# ventmon_t0_5b.net
KiCad netlist of a schematic drawn in EAGLE
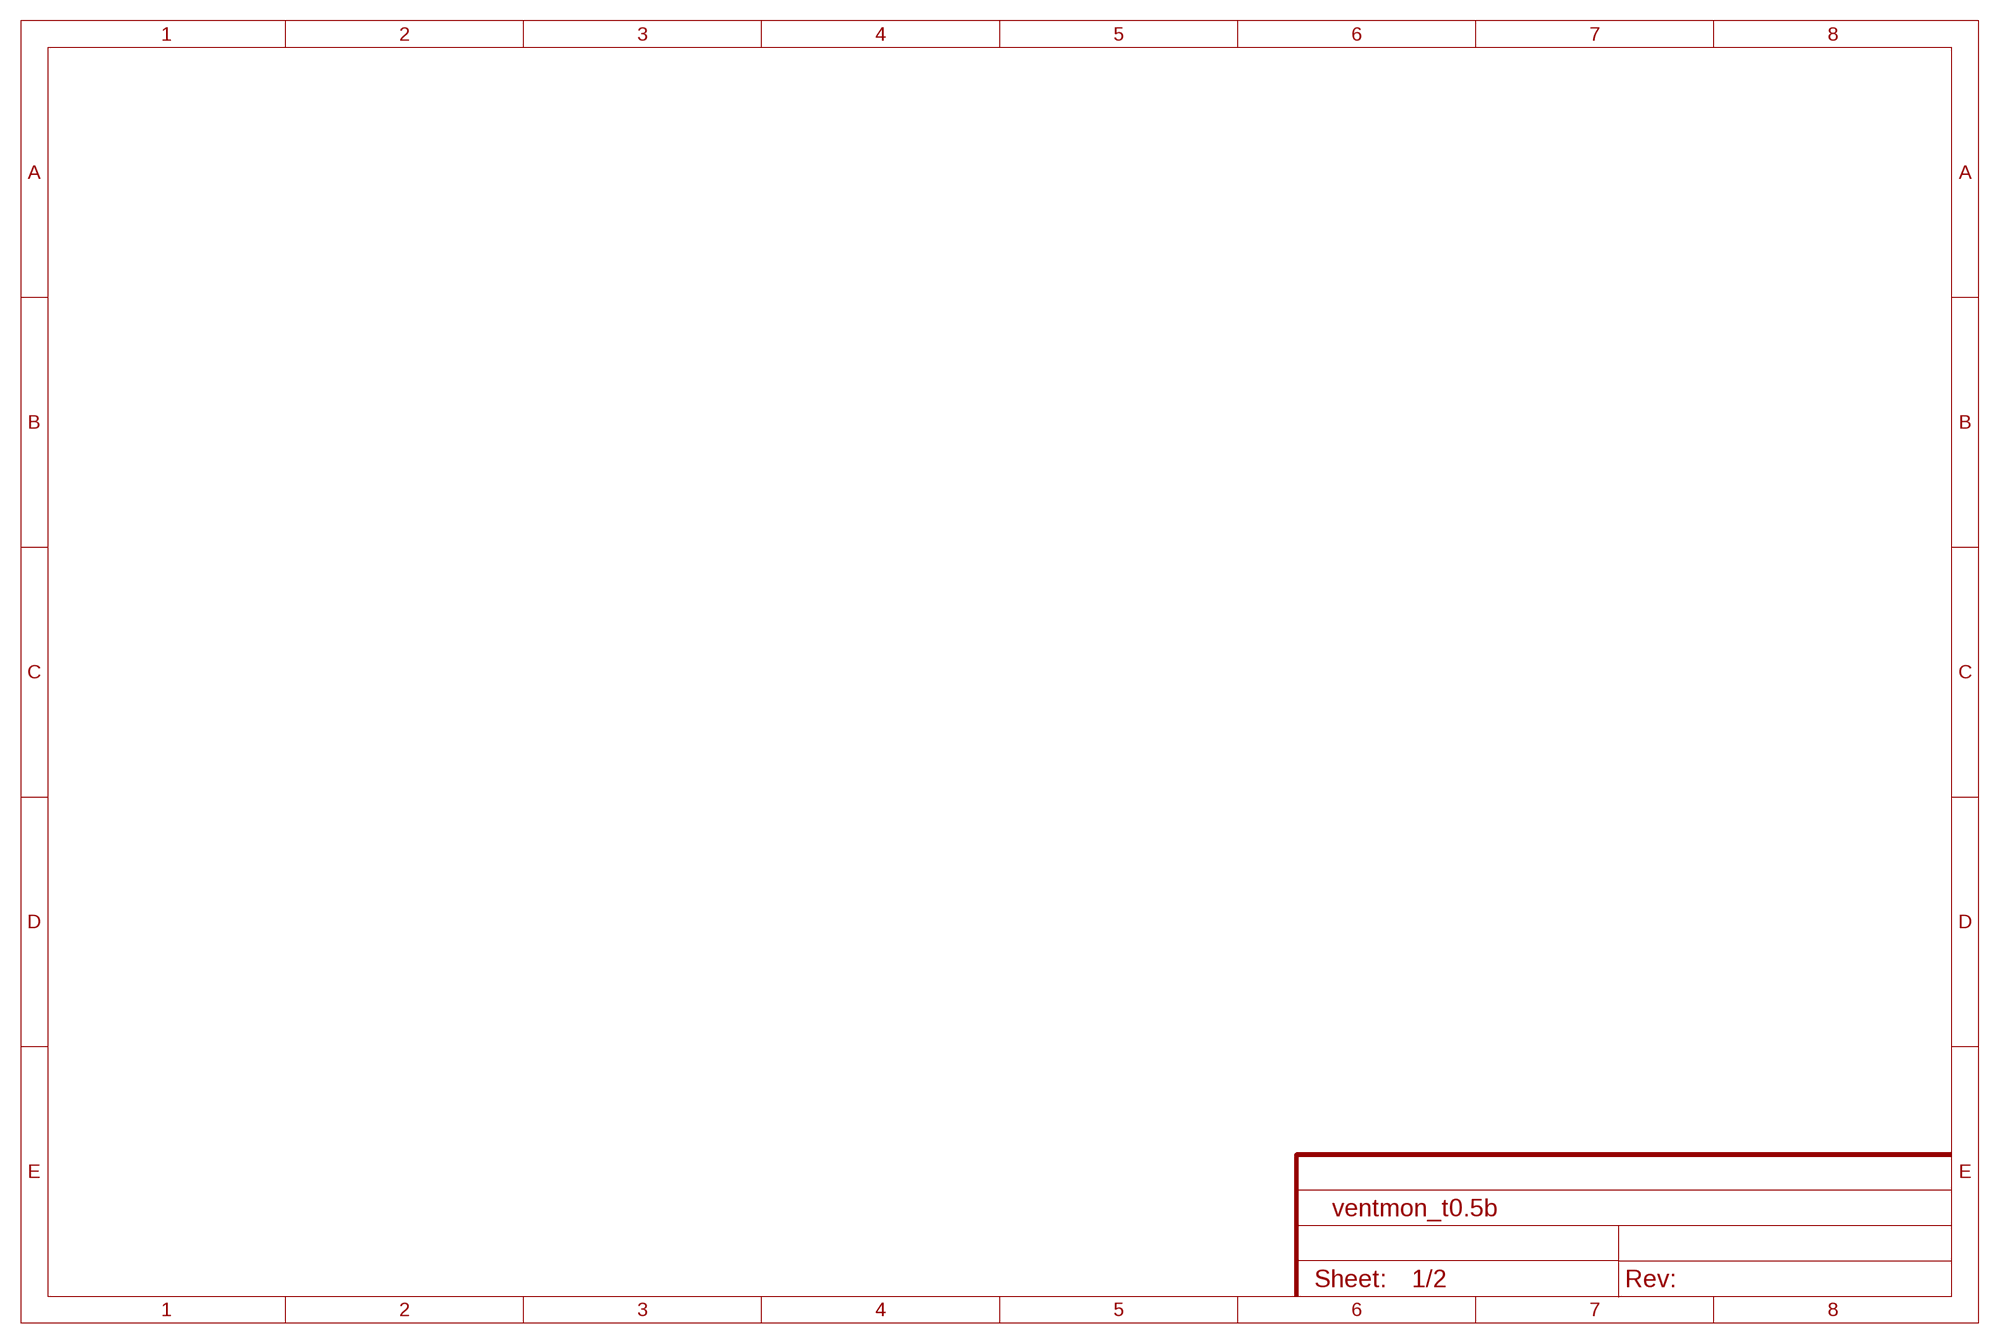
[diagram p0: schematic, sheet 1]
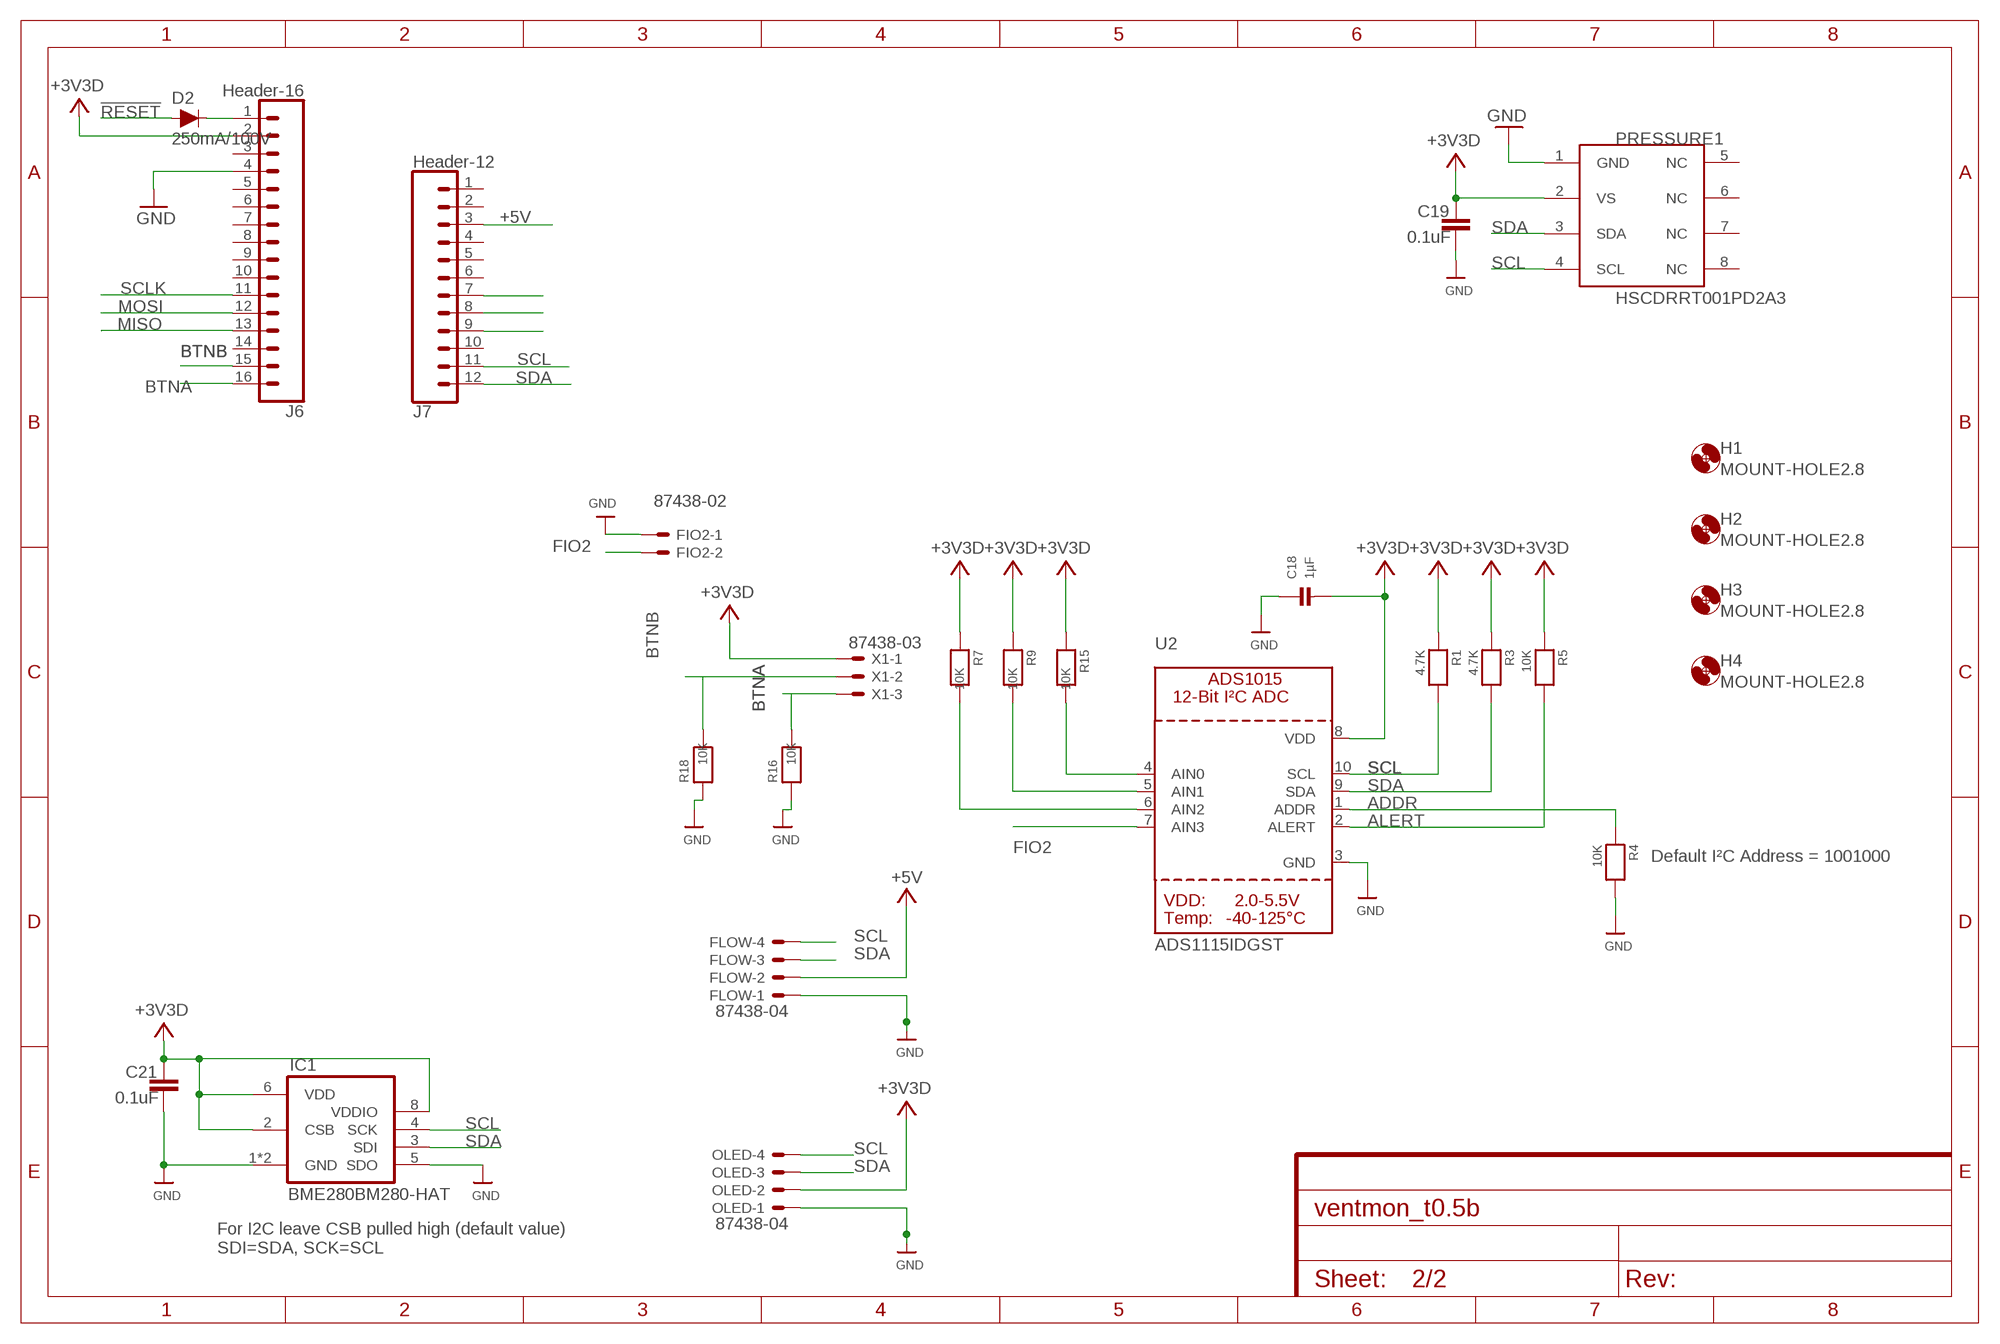
[diagram p1: schematic, sheet 2]

(export (version "E")
  (design (tool "Eeschema 10.0.6"))
  (components
    (comp (ref "C18")
      (value "1µF")
      (footprint "eagle-import:0603")
      (libsource (lib "eagle-import") (part "CAP_CERAMIC0603"))
    )
    (comp (ref "C19")
      (value "0.1uF")
      (footprint "eagle-import:C0402_B")
      (libsource (lib "eagle-import") (part "CAP_1"))
    )
    (comp (ref "C21")
      (value "0.1uF")
      (footprint "eagle-import:C0402_B")
      (libsource (lib "eagle-import") (part "CAP_1"))
    )
    (comp (ref "D2")
      (value "250mA/100V")
      (footprint "eagle-import:SOD-323")
      (libsource (lib "eagle-import") (part "DIODE-BAS16J"))
    )
    (comp (ref "FIO2")
      (value "87438-02")
      (footprint "eagle-import:87438-02")
      (fields (field (name "MF") "MOLEX"))
      (libsource (lib "eagle-import") (part "87438-02"))
    )
    (comp (ref "FLOW")
      (value "87438-04")
      (footprint "eagle-import:87438-04")
      (fields (field (name "MF") "MOLEX"))
      (libsource (lib "eagle-import") (part "87438-04"))
    )
    (comp (ref "H1")
      (value "MOUNT-HOLE2.8")
      (footprint "eagle-import:2,8")
      (fields (field (name "SPICEPREFIX") "X"))
      (libsource (lib "eagle-import") (part "MOUNT-HOLE2.8"))
    )
    (comp (ref "H2")
      (value "MOUNT-HOLE2.8")
      (footprint "eagle-import:2,8")
      (libsource (lib "eagle-import") (part "MOUNT-HOLE2.8"))
    )
    (comp (ref "H3")
      (value "MOUNT-HOLE2.8")
      (footprint "eagle-import:2,8")
      (libsource (lib "eagle-import") (part "MOUNT-HOLE2.8"))
    )
    (comp (ref "H4")
      (value "MOUNT-HOLE2.8")
      (footprint "eagle-import:2,8")
      (libsource (lib "eagle-import") (part "MOUNT-HOLE2.8"))
    )
    (comp (ref "IC1")
      (value "BME280BM280-HAT")
      (footprint "eagle-import:BME280-HAT")
      (libsource (lib "eagle-import") (part "BME280BM280-HAT"))
    )
    (comp (ref "J6")
      (value "Header-16")
      (footprint "eagle-import:1X16")
      (libsource (lib "eagle-import") (part "CONN_16"))
    )
    (comp (ref "J7")
      (value "Header-12")
      (footprint "eagle-import:1X12")
      (libsource (lib "eagle-import") (part "CONN_12"))
    )
    (comp (ref "OLED")
      (value "87438-04")
      (footprint "eagle-import:87438-04")
      (fields (field (name "MF") "MOLEX"))
      (libsource (lib "eagle-import") (part "87438-04"))
    )
    (comp (ref "PRESSURE1")
      (value "HSCDRRT001PD2A3")
      (footprint "eagle-import:DIP1330W46P254L1000H616Q8B")
      (libsource (lib "eagle-import") (part "HSCDRRT001PD2A3"))
    )
    (comp (ref "R1")
      (value "4.7K")
      (footprint "eagle-import:0603")
      (libsource (lib "eagle-import") (part "RESISTOR0603"))
    )
    (comp (ref "R3")
      (value "4.7K")
      (footprint "eagle-import:0603")
      (libsource (lib "eagle-import") (part "RESISTOR0603"))
    )
    (comp (ref "R4")
      (value "10K")
      (footprint "eagle-import:0603")
      (libsource (lib "eagle-import") (part "RESISTOR0603"))
    )
    (comp (ref "R5")
      (value "10K")
      (footprint "eagle-import:0603")
      (libsource (lib "eagle-import") (part "RESISTOR0603"))
    )
    (comp (ref "R7")
      (value "10K")
      (footprint "eagle-import:0603")
      (libsource (lib "eagle-import") (part "RESISTOR0603"))
    )
    (comp (ref "R9")
      (value "10K")
      (footprint "eagle-import:0603")
      (libsource (lib "eagle-import") (part "RESISTOR0603"))
    )
    (comp (ref "R15")
      (value "10K")
      (footprint "eagle-import:0603")
      (libsource (lib "eagle-import") (part "RESISTOR0603"))
    )
    (comp (ref "R16")
      (value "10K")
      (footprint "eagle-import:0603")
      (libsource (lib "eagle-import") (part "RESISTOR0603"))
    )
    (comp (ref "R18")
      (value "10K")
      (footprint "eagle-import:0603")
      (libsource (lib "eagle-import") (part "RESISTOR0603"))
    )
    (comp (ref "U2")
      (value "ADS1115IDGST")
      (footprint "eagle-import:MSOP10")
      (libsource (lib "eagle-import") (part "ADC_ADS1015"))
    )
    (comp (ref "X1")
      (value "87438-03")
      (footprint "eagle-import:87438-03")
      (fields (field (name "MF") "MOLEX"))
      (libsource (lib "eagle-import") (part "87438-03"))
    )
  )
  (nets
    (net (code "1") (name "+3V3") (class "Default")
      (node (ref "C18") (pin "2") (pinfunction "P$2_2") (pintype "passive"))
      (node (ref "C19") (pin "2") (pinfunction "P$2_2") (pintype "passive"))
      (node (ref "C21") (pin "2") (pinfunction "P$2_2") (pintype "passive"))
      (node (ref "IC1") (pin "2") (pinfunction "CSB_2") (pintype "input"))
      (node (ref "IC1") (pin "6") (pinfunction "VDD_6") (pintype "power_in"))
      (node (ref "IC1") (pin "8") (pinfunction "VDDIO_8") (pintype "power_in"))
      (node (ref "J6") (pin "2") (pinfunction "2_2") (pintype "passive"))
      (node (ref "OLED") (pin "2") (pinfunction "S_2") (pintype "passive"))
      (node (ref "PRESSURE1") (pin "2") (pinfunction "VS_2") (pintype "bidirectional"))
      (node (ref "R1") (pin "1") (pinfunction "1_1") (pintype "passive"))
      (node (ref "R15") (pin "1") (pinfunction "1_1") (pintype "passive"))
      (node (ref "R3") (pin "1") (pinfunction "1_1") (pintype "passive"))
      (node (ref "R5") (pin "1") (pinfunction "1_1") (pintype "passive"))
      (node (ref "R7") (pin "1") (pinfunction "1_1") (pintype "passive"))
      (node (ref "R9") (pin "1") (pinfunction "1_1") (pintype "passive"))
      (node (ref "U2") (pin "8") (pinfunction "VDD_8") (pintype "bidirectional"))
      (node (ref "X1") (pin "1") (pinfunction "S_1") (pintype "passive"))
    )
    (net (code "2") (name "+5V") (class "Default")
      (node (ref "FLOW") (pin "2") (pinfunction "S_2") (pintype "passive"))
      (node (ref "J7") (pin "3") (pinfunction "3_3") (pintype "passive"))
    )
    (net (code "3") (name "ADDR") (class "Default")
      (node (ref "R4") (pin "1") (pinfunction "1_1") (pintype "passive"))
      (node (ref "U2") (pin "1") (pinfunction "ADDR_1") (pintype "bidirectional"))
    )
    (net (code "4") (name "ALERT") (class "Default")
      (node (ref "R5") (pin "2") (pinfunction "2_2") (pintype "passive"))
      (node (ref "U2") (pin "2") (pinfunction "ALERT_2") (pintype "bidirectional"))
    )
    (net (code "5") (name "BTNA") (class "Default")
      (node (ref "J6") (pin "16") (pinfunction "16_16") (pintype "passive"))
      (node (ref "R16") (pin "2") (pinfunction "2_2") (pintype "passive"))
      (node (ref "X1") (pin "3") (pinfunction "S_3") (pintype "passive"))
    )
    (net (code "6") (name "BTNB") (class "Default")
      (node (ref "J6") (pin "15") (pinfunction "15_15") (pintype "passive"))
      (node (ref "R18") (pin "2") (pinfunction "2_2") (pintype "passive"))
      (node (ref "X1") (pin "2") (pinfunction "S_2") (pintype "passive"))
    )
    (net (code "7") (name "FIO2") (class "Default")
      (node (ref "FIO2") (pin "2") (pinfunction "S_2") (pintype "passive"))
      (node (ref "U2") (pin "7") (pinfunction "AIN3_7") (pintype "bidirectional"))
    )
    (net (code "8") (name "GND") (class "Default")
      (node (ref "C18") (pin "1") (pinfunction "P$1_1") (pintype "passive"))
      (node (ref "C19") (pin "1") (pinfunction "P$1_1") (pintype "passive"))
      (node (ref "C21") (pin "1") (pinfunction "P$1_1") (pintype "passive"))
      (node (ref "FIO2") (pin "1") (pinfunction "S_1") (pintype "passive"))
      (node (ref "FLOW") (pin "1") (pinfunction "S_1") (pintype "passive"))
      (node (ref "IC1") (pin "1") (pinfunction "GND_1") (pintype "power_in"))
      (node (ref "IC1") (pin "5") (pinfunction "SDO_5") (pintype "input"))
      (node (ref "IC1") (pin "7") (pinfunction "GND_7") (pintype "power_in"))
      (node (ref "J6") (pin "4") (pinfunction "4_4") (pintype "passive"))
      (node (ref "OLED") (pin "1") (pinfunction "S_1") (pintype "passive"))
      (node (ref "PRESSURE1") (pin "1") (pinfunction "GND_1") (pintype "bidirectional"))
      (node (ref "R16") (pin "1") (pinfunction "1_1") (pintype "passive"))
      (node (ref "R18") (pin "1") (pinfunction "1_1") (pintype "passive"))
      (node (ref "R4") (pin "2") (pinfunction "2_2") (pintype "passive"))
      (node (ref "U2") (pin "3") (pinfunction "GND_3") (pintype "bidirectional"))
    )
    (net (code "9") (name "MISO") (class "Default")
      (node (ref "J6") (pin "13") (pinfunction "13_13") (pintype "passive"))
    )
    (net (code "10") (name "MOSI") (class "Default")
      (node (ref "J6") (pin "12") (pinfunction "12_12") (pintype "passive"))
    )
    (net (code "11") (name "Net-(D2-PadC)") (class "Default")
      (node (ref "D2") (pin "C") (pinfunction "C_C") (pintype "passive"))
      (node (ref "J6") (pin "1") (pinfunction "1_1") (pintype "passive"))
    )
    (net (code "12") (name "Net-(U2-AIN0)") (class "Default")
      (node (ref "R15") (pin "2") (pinfunction "2_2") (pintype "passive"))
      (node (ref "U2") (pin "4") (pinfunction "AIN0_4") (pintype "bidirectional"))
    )
    (net (code "13") (name "Net-(U2-AIN1)") (class "Default")
      (node (ref "R9") (pin "2") (pinfunction "2_2") (pintype "passive"))
      (node (ref "U2") (pin "5") (pinfunction "AIN1_5") (pintype "bidirectional"))
    )
    (net (code "14") (name "Net-(U2-AIN2)") (class "Default")
      (node (ref "R7") (pin "2") (pinfunction "2_2") (pintype "passive"))
      (node (ref "U2") (pin "6") (pinfunction "AIN2_6") (pintype "bidirectional"))
    )
    (net (code "15") (name "SCL") (class "Default")
      (node (ref "FLOW") (pin "4") (pinfunction "S_4") (pintype "passive"))
      (node (ref "IC1") (pin "4") (pinfunction "SCK_4") (pintype "bidirectional"))
      (node (ref "J7") (pin "11") (pinfunction "11_11") (pintype "passive"))
      (node (ref "OLED") (pin "4") (pinfunction "S_4") (pintype "passive"))
      (node (ref "PRESSURE1") (pin "4") (pinfunction "SCL_4") (pintype "bidirectional"))
      (node (ref "R1") (pin "2") (pinfunction "2_2") (pintype "passive"))
      (node (ref "U2") (pin "10") (pinfunction "SCL_10") (pintype "bidirectional"))
    )
    (net (code "16") (name "SCLK") (class "Default")
      (node (ref "J6") (pin "11") (pinfunction "11_11") (pintype "passive"))
    )
    (net (code "17") (name "SDA") (class "Default")
      (node (ref "FLOW") (pin "3") (pinfunction "S_3") (pintype "passive"))
      (node (ref "IC1") (pin "3") (pinfunction "SDI_3") (pintype "bidirectional"))
      (node (ref "J7") (pin "12") (pinfunction "12_12") (pintype "passive"))
      (node (ref "OLED") (pin "3") (pinfunction "S_3") (pintype "passive"))
      (node (ref "PRESSURE1") (pin "3") (pinfunction "SDA_3") (pintype "bidirectional"))
      (node (ref "R3") (pin "2") (pinfunction "2_2") (pintype "passive"))
      (node (ref "U2") (pin "9") (pinfunction "SDA_9") (pintype "bidirectional"))
    )
    (net (code "18") (name "unconnected-(J6-Pad3)") (class "Default")
      (node (ref "J6") (pin "3") (pinfunction "3_3") (pintype "passive"))
    )
    (net (code "19") (name "unconnected-(J6-Pad5)") (class "Default")
      (node (ref "J6") (pin "5") (pinfunction "5_5") (pintype "passive"))
    )
    (net (code "20") (name "unconnected-(J6-Pad6)") (class "Default")
      (node (ref "J6") (pin "6") (pinfunction "6_6") (pintype "passive"))
    )
    (net (code "21") (name "unconnected-(J6-Pad7)") (class "Default")
      (node (ref "J6") (pin "7") (pinfunction "7_7") (pintype "passive"))
    )
    (net (code "22") (name "unconnected-(J6-Pad8)") (class "Default")
      (node (ref "J6") (pin "8") (pinfunction "8_8") (pintype "passive"))
    )
    (net (code "23") (name "unconnected-(J6-Pad9)") (class "Default")
      (node (ref "J6") (pin "9") (pinfunction "9_9") (pintype "passive"))
    )
    (net (code "24") (name "unconnected-(J6-Pad10)") (class "Default")
      (node (ref "J6") (pin "10") (pinfunction "10_10") (pintype "passive"))
    )
    (net (code "25") (name "unconnected-(J6-Pad14)") (class "Default")
      (node (ref "J6") (pin "14") (pinfunction "14_14") (pintype "passive"))
    )
    (net (code "26") (name "unconnected-(J7-Pad1)") (class "Default")
      (node (ref "J7") (pin "1") (pinfunction "1_1") (pintype "passive"))
    )
    (net (code "27") (name "unconnected-(J7-Pad2)") (class "Default")
      (node (ref "J7") (pin "2") (pinfunction "2_2") (pintype "passive"))
    )
    (net (code "28") (name "unconnected-(J7-Pad4)") (class "Default")
      (node (ref "J7") (pin "4") (pinfunction "4_4") (pintype "passive"))
    )
    (net (code "29") (name "unconnected-(J7-Pad5)") (class "Default")
      (node (ref "J7") (pin "5") (pinfunction "5_5") (pintype "passive"))
    )
    (net (code "30") (name "unconnected-(J7-Pad6)") (class "Default")
      (node (ref "J7") (pin "6") (pinfunction "6_6") (pintype "passive"))
    )
    (net (code "31") (name "unconnected-(J7-Pad7)") (class "Default")
      (node (ref "J7") (pin "7") (pinfunction "7_7") (pintype "passive"))
    )
    (net (code "32") (name "unconnected-(J7-Pad8)") (class "Default")
      (node (ref "J7") (pin "8") (pinfunction "8_8") (pintype "passive"))
    )
    (net (code "33") (name "unconnected-(J7-Pad9)") (class "Default")
      (node (ref "J7") (pin "9") (pinfunction "9_9") (pintype "passive"))
    )
    (net (code "34") (name "unconnected-(J7-Pad10)") (class "Default")
      (node (ref "J7") (pin "10") (pinfunction "10_10") (pintype "passive"))
    )
    (net (code "35") (name "unconnected-(PRESSURE1-NC-Pad5)") (class "Default")
      (node (ref "PRESSURE1") (pin "5") (pinfunction "NC_5") (pintype "bidirectional"))
    )
    (net (code "36") (name "unconnected-(PRESSURE1-NC-Pad6)") (class "Default")
      (node (ref "PRESSURE1") (pin "6") (pinfunction "NC_6") (pintype "bidirectional"))
    )
    (net (code "37") (name "unconnected-(PRESSURE1-NC-Pad7)") (class "Default")
      (node (ref "PRESSURE1") (pin "7") (pinfunction "NC_7") (pintype "bidirectional"))
    )
    (net (code "38") (name "unconnected-(PRESSURE1-NC-Pad8)") (class "Default")
      (node (ref "PRESSURE1") (pin "8") (pinfunction "NC_8") (pintype "bidirectional"))
    )
    (net (code "39") (name "~{RESET}") (class "Default")
      (node (ref "D2") (pin "A") (pinfunction "A_A") (pintype "passive"))
    )
  )
)
